# v2-scratch.net
KiCad netlist of a schematic drawn in EAGLE
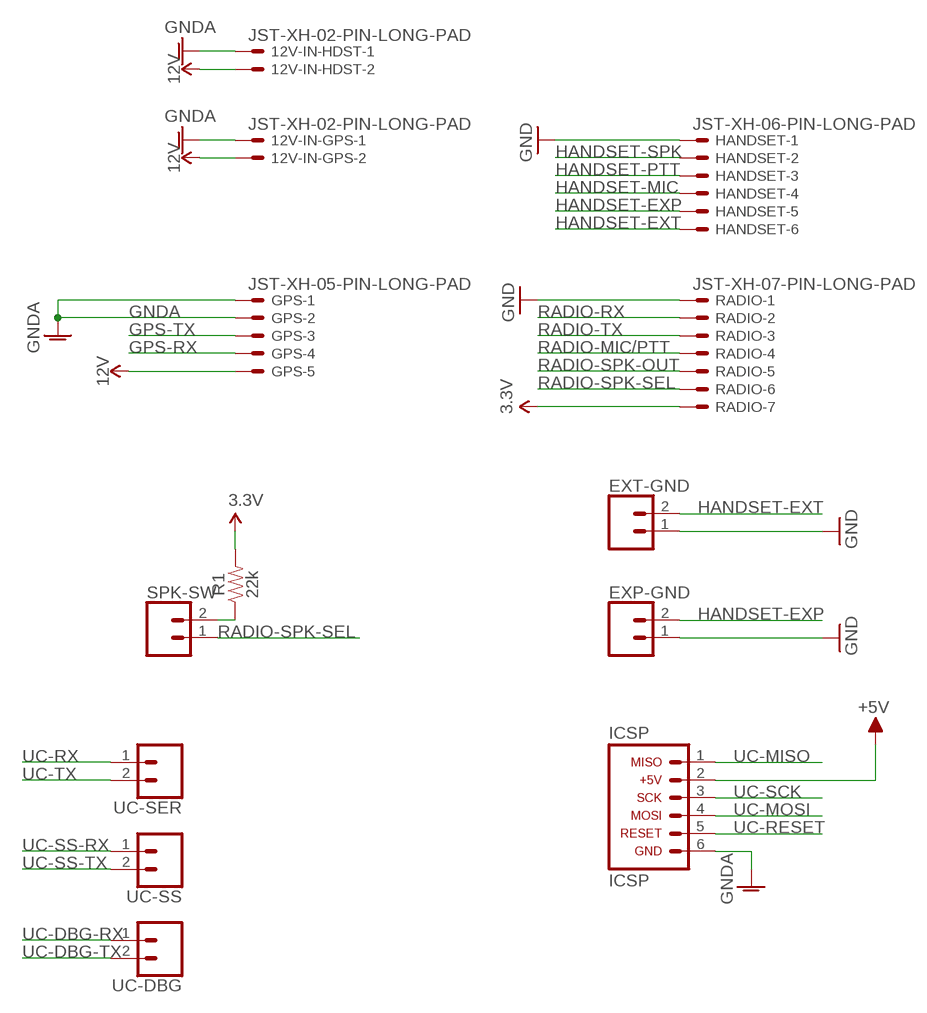
[diagram p0: schematic, sheet 1, part 1 of 2]
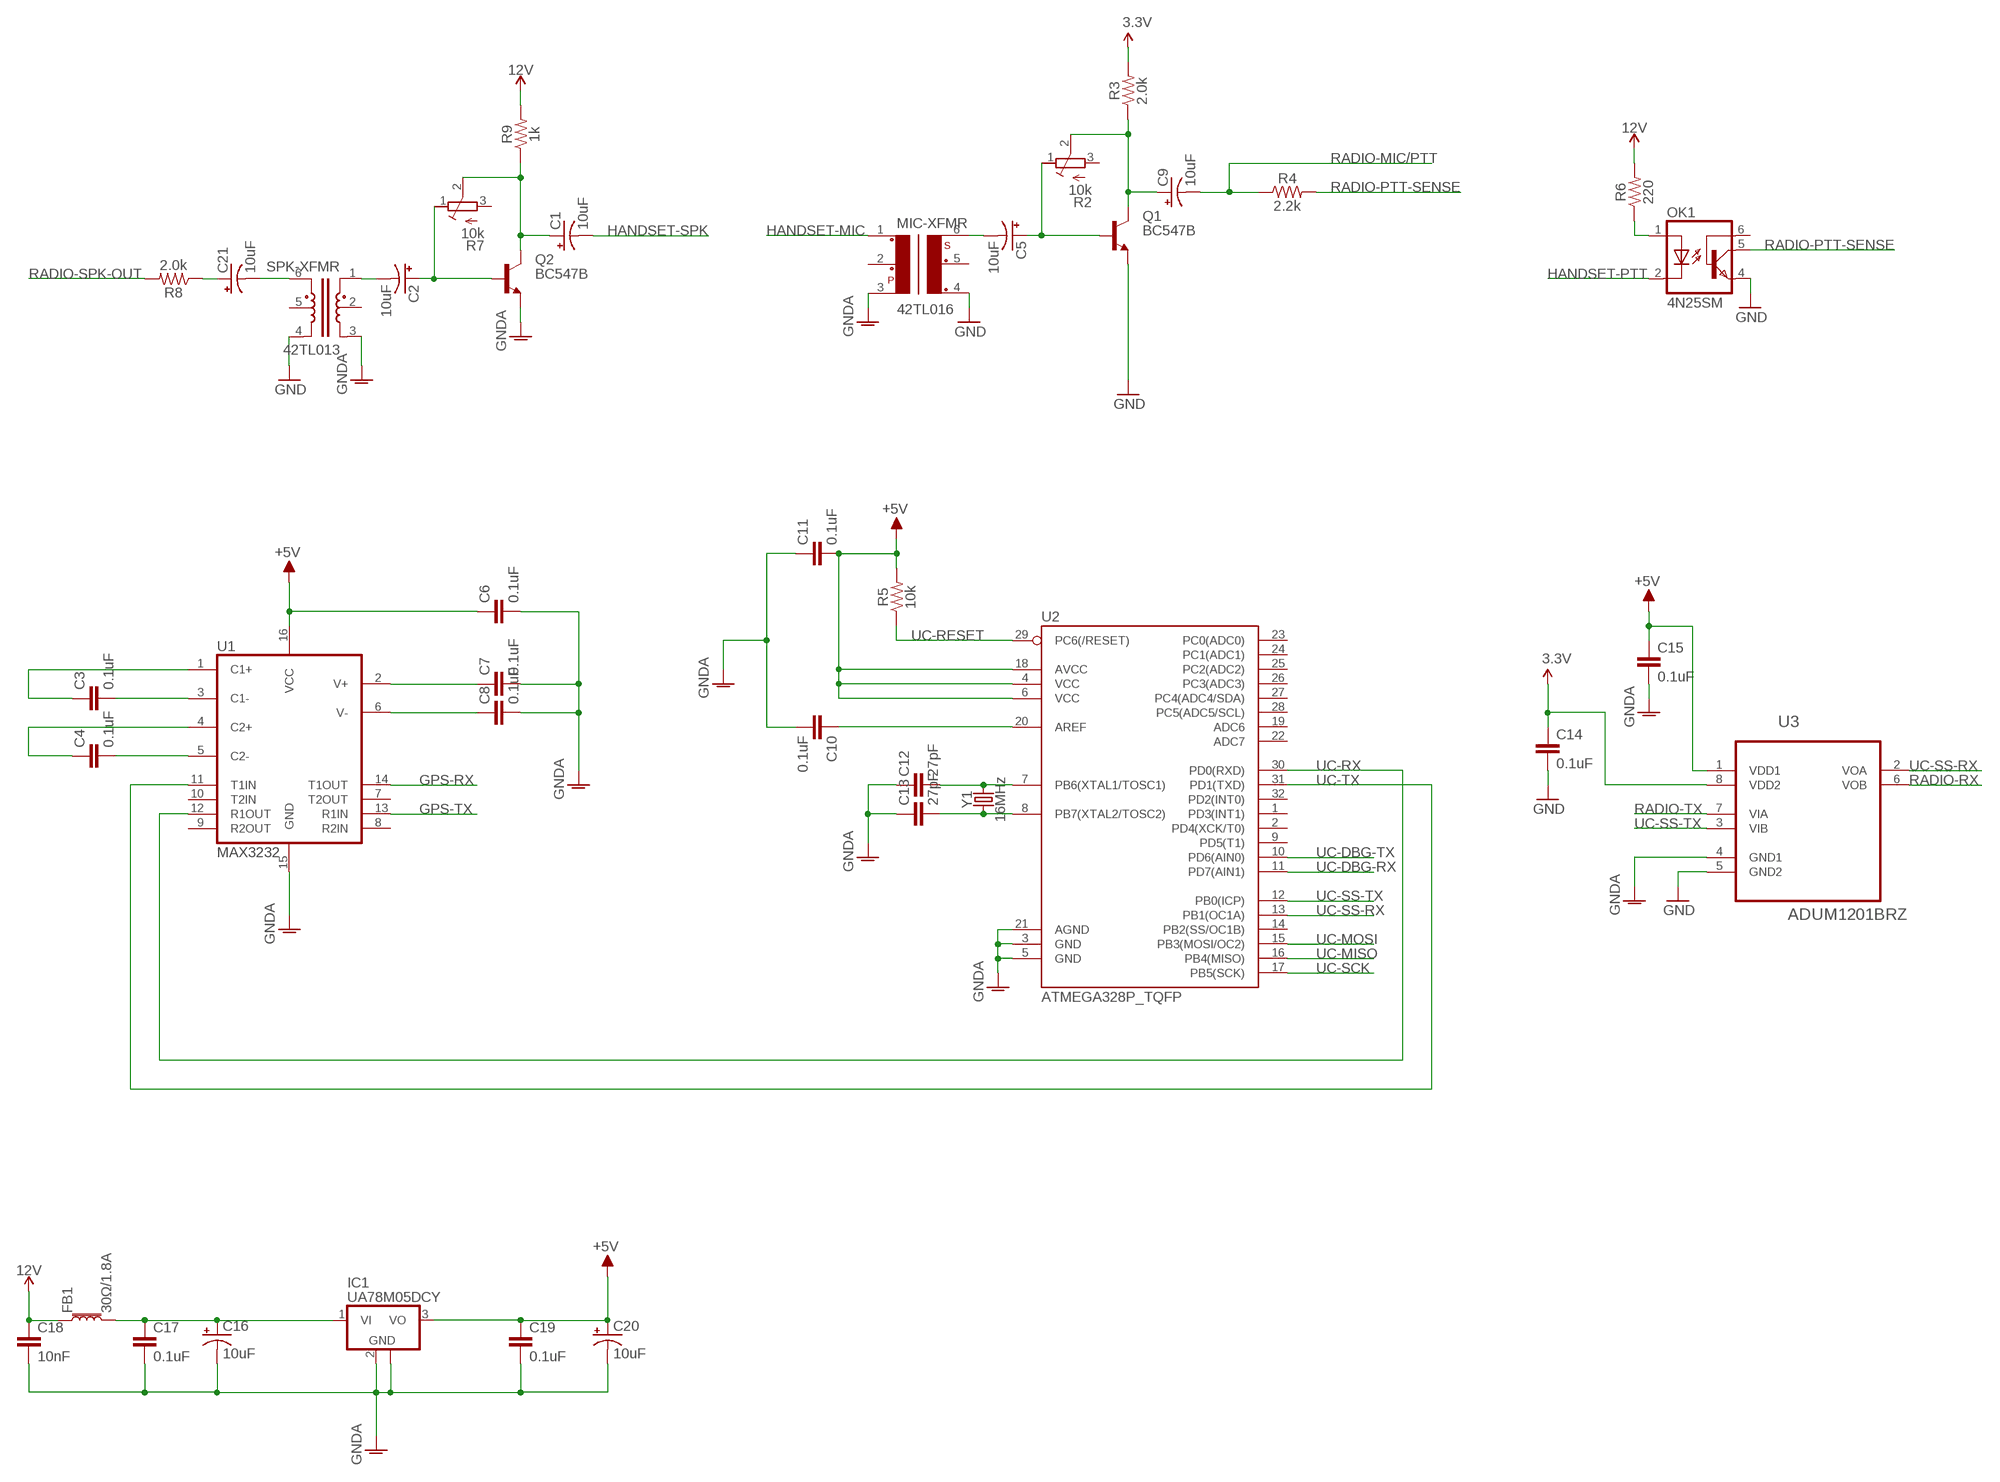
[diagram p1: schematic, sheet 1, part 2 of 2]

(export (version "E")
  (design (tool "Eeschema 10.0.6"))
  (components
    (comp (ref "12V-IN-GPS")
      (value "JST-XH-02-PIN-LONG-PAD")
      (footprint "eagle-import:JST-XH-02-PACKAGE-LONG-PAD")
      (libsource (lib "eagle-import") (part "JST-XH-02-PIN-LONG-PAD"))
    )
    (comp (ref "12V-IN-HDST")
      (value "JST-XH-02-PIN-LONG-PAD")
      (footprint "eagle-import:JST-XH-02-PACKAGE-LONG-PAD")
      (libsource (lib "eagle-import") (part "JST-XH-02-PIN-LONG-PAD"))
    )
    (comp (ref "C1")
      (value "10uF")
      (footprint "eagle-import:E2,5-5")
      (libsource (lib "eagle-import") (part "CPOL-USE2.5-5"))
    )
    (comp (ref "C2")
      (value "10uF")
      (footprint "eagle-import:E2,5-5")
      (libsource (lib "eagle-import") (part "CPOL-USE2.5-5"))
    )
    (comp (ref "C3")
      (value "0.1uF")
      (footprint "eagle-import:0603")
      (libsource (lib "eagle-import") (part "0.1UF-0603-25V-5%"))
    )
    (comp (ref "C4")
      (value "0.1uF")
      (footprint "eagle-import:0603")
      (libsource (lib "eagle-import") (part "0.1UF-0603-25V-5%"))
    )
    (comp (ref "C5")
      (value "10uF")
      (footprint "eagle-import:E2,5-5")
      (libsource (lib "eagle-import") (part "CPOL-USE2.5-5"))
    )
    (comp (ref "C6")
      (value "0.1uF")
      (footprint "eagle-import:0603")
      (libsource (lib "eagle-import") (part "0.1UF-0603-25V-5%"))
    )
    (comp (ref "C7")
      (value "0.1uF")
      (footprint "eagle-import:0603")
      (libsource (lib "eagle-import") (part "0.1UF-0603-25V-5%"))
    )
    (comp (ref "C8")
      (value "0.1uF")
      (footprint "eagle-import:0603")
      (libsource (lib "eagle-import") (part "0.1UF-0603-25V-5%"))
    )
    (comp (ref "C9")
      (value "10uF")
      (footprint "eagle-import:E2,5-5")
      (libsource (lib "eagle-import") (part "CPOL-USE2.5-5"))
    )
    (comp (ref "C10")
      (value "0.1uF")
      (footprint "eagle-import:0603")
      (libsource (lib "eagle-import") (part "0.1UF-0603-25V-5%"))
    )
    (comp (ref "C11")
      (value "0.1uF")
      (footprint "eagle-import:0603")
      (libsource (lib "eagle-import") (part "0.1UF-0603-25V-5%"))
    )
    (comp (ref "C12")
      (value "27pF")
      (footprint "eagle-import:0603")
      (libsource (lib "eagle-import") (part "27PF-0603-50V-5%"))
    )
    (comp (ref "C13")
      (value "27pF")
      (footprint "eagle-import:0603")
      (libsource (lib "eagle-import") (part "27PF-0603-50V-5%"))
    )
    (comp (ref "C14")
      (value "0.1uF")
      (footprint "eagle-import:0603")
      (libsource (lib "eagle-import") (part "0.1UF-0603-25V-5%"))
    )
    (comp (ref "C15")
      (value "0.1uF")
      (footprint "eagle-import:0603")
      (libsource (lib "eagle-import") (part "0.1UF-0603-25V-5%"))
    )
    (comp (ref "C16")
      (value "10uF")
      (footprint "eagle-import:E2,5-5")
      (libsource (lib "eagle-import") (part "CPOL-USE2.5-5"))
    )
    (comp (ref "C17")
      (value "0.1uF")
      (footprint "eagle-import:0603")
      (libsource (lib "eagle-import") (part "0.1UF-0603-25V-5%"))
    )
    (comp (ref "C18")
      (value "10nF")
      (footprint "eagle-import:0603")
      (libsource (lib "eagle-import") (part "10NF-0603-50V-10%"))
    )
    (comp (ref "C19")
      (value "0.1uF")
      (footprint "eagle-import:0603")
      (libsource (lib "eagle-import") (part "0.1UF-0603-25V-5%"))
    )
    (comp (ref "C20")
      (value "10uF")
      (footprint "eagle-import:E2,5-5")
      (libsource (lib "eagle-import") (part "CPOL-USE2.5-5"))
    )
    (comp (ref "C21")
      (value "10uF")
      (footprint "eagle-import:E2,5-5")
      (libsource (lib "eagle-import") (part "CPOL-USE2.5-5"))
    )
    (comp (ref "EXP-GND")
      (value "CONN_02")
      (footprint "eagle-import:1X02")
      (libsource (lib "eagle-import") (part "CONN_02"))
    )
    (comp (ref "EXT-GND")
      (value "CONN_02")
      (footprint "eagle-import:1X02")
      (libsource (lib "eagle-import") (part "CONN_02"))
    )
    (comp (ref "FB1")
      (value "30Ω/1.8A")
      (footprint "eagle-import:0603")
      (libsource (lib "eagle-import") (part "FERRITE_BEAD-0603"))
    )
    (comp (ref "GPS")
      (value "JST-XH-05-PIN-LONG-PAD")
      (footprint "eagle-import:JST-XH-05-PACKAGE-LONG-PAD")
      (libsource (lib "eagle-import") (part "JST-XH-05-PIN-LONG-PAD"))
    )
    (comp (ref "HANDSET")
      (value "JST-XH-06-PIN-LONG-PAD")
      (footprint "eagle-import:JST-XH-06-PACKAGE-LONG-PAD")
      (libsource (lib "eagle-import") (part "JST-XH-06-PIN-LONG-PAD"))
    )
    (comp (ref "IC1")
      (value "UA78M05DCY")
      (footprint "eagle-import:SOT223")
      (libsource (lib "eagle-import") (part "UA78MDCY05"))
    )
    (comp (ref "ICSP")
      (value "ARDUINO_CONN-ICSP")
      (footprint "eagle-import:CONN-2X03")
      (libsource (lib "eagle-import") (part "ARDUINO_CONN-ICSP"))
    )
    (comp (ref "MIC-XFMR")
      (value "42TL016")
      (footprint "eagle-import:42TL")
      (libsource (lib "eagle-import") (part "42T?L016"))
    )
    (comp (ref "OK1")
      (value "4N25SM")
      (footprint "eagle-import:DIL6-SMD")
      (fields (field (name "MF") "FAIRCHILD SEMICONDUCTOR"))
      (libsource (lib "eagle-import") (part "4N?MS25"))
    )
    (comp (ref "Q1")
      (value "BC547B")
      (footprint "eagle-import:TO92")
      (libsource (lib "eagle-import") (part "BC547B"))
    )
    (comp (ref "Q2")
      (value "BC547B")
      (footprint "eagle-import:TO92")
      (libsource (lib "eagle-import") (part "BC547B"))
    )
    (comp (ref "R1")
      (value "22k")
      (footprint "eagle-import:0603")
      (libsource (lib "eagle-import") (part "22KOHM-0603-1/10W-1%"))
    )
    (comp (ref "R2")
      (value "10k")
      (footprint "eagle-import:RTRIMT93YA")
      (libsource (lib "eagle-import") (part "R-TRIMMT93YA"))
    )
    (comp (ref "R3")
      (value "2.0k")
      (footprint "eagle-import:0603")
      (libsource (lib "eagle-import") (part "2.0KOHM-0603-1/10W-5%"))
    )
    (comp (ref "R4")
      (value "2.2k")
      (footprint "eagle-import:0603")
      (libsource (lib "eagle-import") (part "2.2KOHM-0603-1/10W-1%"))
    )
    (comp (ref "R5")
      (value "10k")
      (footprint "eagle-import:0603")
      (libsource (lib "eagle-import") (part "10KOHM-0603-1/10W-1%"))
    )
    (comp (ref "R6")
      (value "220")
      (footprint "eagle-import:0603")
      (libsource (lib "eagle-import") (part "220OHM-0603-1/10W-1%"))
    )
    (comp (ref "R7")
      (value "10k")
      (footprint "eagle-import:RTRIMT93YA")
      (libsource (lib "eagle-import") (part "R-TRIMMT93YA"))
    )
    (comp (ref "R8")
      (value "2.0k")
      (footprint "eagle-import:0603")
      (libsource (lib "eagle-import") (part "2.0KOHM-0603-1/10W-5%"))
    )
    (comp (ref "R9")
      (value "1k")
      (footprint "eagle-import:0603")
      (libsource (lib "eagle-import") (part "1KOHM-0603-1/10W-1%"))
    )
    (comp (ref "RADIO")
      (value "JST-XH-07-PIN-LONG-PAD")
      (footprint "eagle-import:JST-XH-07-PACKAGE-LONG-PAD")
      (libsource (lib "eagle-import") (part "JST-XH-07-PIN-LONG-PAD"))
    )
    (comp (ref "SPK-SW")
      (value "CONN_02")
      (footprint "eagle-import:1X02")
      (libsource (lib "eagle-import") (part "CONN_02"))
    )
    (comp (ref "SPK-XFMR")
      (value "42TL013")
      (footprint "eagle-import:TRANS_EI-14")
      (libsource (lib "eagle-import") (part "42TL013"))
    )
    (comp (ref "U1")
      (value "MAX3232")
      (footprint "eagle-import:SO16")
      (libsource (lib "eagle-import") (part "MAX2323SOIC16"))
    )
    (comp (ref "U2")
      (value "ATMEGA328P_TQFP")
      (footprint "eagle-import:TQFP32-08")
      (libsource (lib "eagle-import") (part "ATMEGA328P_TQFP"))
    )
    (comp (ref "U3")
      (value "ADUM1201BRZ")
      (footprint "eagle-import:SOIC127P600X175-8N")
      (libsource (lib "eagle-import") (part "ADUM1201BRZ"))
    )
    (comp (ref "UC-DBG")
      (value "CONN_02")
      (footprint "eagle-import:1X02")
      (libsource (lib "eagle-import") (part "CONN_02"))
    )
    (comp (ref "UC-SER")
      (value "CONN_02")
      (footprint "eagle-import:1X02")
      (libsource (lib "eagle-import") (part "CONN_02"))
    )
    (comp (ref "UC-SS")
      (value "CONN_02")
      (footprint "eagle-import:1X02")
      (libsource (lib "eagle-import") (part "CONN_02"))
    )
    (comp (ref "Y1")
      (value "16MHz")
      (footprint "eagle-import:HC49US")
      (libsource (lib "eagle-import") (part "CRYSTAL-16MHZPTH-HC49US"))
    )
  )
  (nets
    (net (code "1") (name "+5V") (class "Default")
      (node (ref "C11") (pin "2") (pinfunction "2_2") (pintype "passive"))
      (node (ref "C15") (pin "1") (pinfunction "1_1") (pintype "passive"))
      (node (ref "C19") (pin "1") (pinfunction "1_1") (pintype "passive"))
      (node (ref "C20") (pin "+") (pinfunction "+_+") (pintype "passive"))
      (node (ref "C6") (pin "1") (pinfunction "1_1") (pintype "passive"))
      (node (ref "IC1") (pin "3") (pinfunction "VO_3") (pintype "passive"))
      (node (ref "ICSP") (pin "2") (pinfunction "2_2") (pintype "passive"))
      (node (ref "R5") (pin "2") (pinfunction "2_2") (pintype "passive"))
      (node (ref "U1") (pin "16") (pinfunction "VCC_16") (pintype "bidirectional"))
      (node (ref "U2") (pin "18") (pinfunction "AVCC_18") (pintype "bidirectional"))
      (node (ref "U2") (pin "4") (pinfunction "VCC_4") (pintype "bidirectional"))
      (node (ref "U2") (pin "6") (pinfunction "VCC_6") (pintype "bidirectional"))
      (node (ref "U3") (pin "1") (pinfunction "VDD1_1") (pintype "power_in"))
    )
    (net (code "2") (name "/GPS-RX") (class "Default")
      (node (ref "GPS") (pin "4") (pinfunction "S_4") (pintype "passive"))
      (node (ref "U1") (pin "14") (pinfunction "T1OUT_14") (pintype "output"))
    )
    (net (code "3") (name "/GPS-TX") (class "Default")
      (node (ref "GPS") (pin "3") (pinfunction "S_3") (pintype "passive"))
      (node (ref "U1") (pin "13") (pinfunction "R1IN_13") (pintype "input"))
    )
    (net (code "4") (name "/HANDSET-EXP") (class "Default")
      (node (ref "EXP-GND") (pin "2") (pinfunction "2_2") (pintype "passive"))
      (node (ref "HANDSET") (pin "5") (pinfunction "S_5") (pintype "passive"))
    )
    (net (code "5") (name "/HANDSET-EXT") (class "Default")
      (node (ref "EXT-GND") (pin "2") (pinfunction "2_2") (pintype "passive"))
      (node (ref "HANDSET") (pin "6") (pinfunction "S_6") (pintype "passive"))
    )
    (net (code "6") (name "/HANDSET-MIC") (class "Default")
      (node (ref "HANDSET") (pin "4") (pinfunction "S_4") (pintype "passive"))
      (node (ref "MIC-XFMR") (pin "1") (pinfunction "1_1") (pintype "passive"))
    )
    (net (code "7") (name "/HANDSET-PTT") (class "Default")
      (node (ref "HANDSET") (pin "3") (pinfunction "S_3") (pintype "passive"))
      (node (ref "OK1") (pin "2") (pinfunction "C_2") (pintype "passive"))
    )
    (net (code "8") (name "/HANDSET-SPK") (class "Default")
      (node (ref "C1") (pin "-") (pinfunction "-_-") (pintype "passive"))
      (node (ref "HANDSET") (pin "2") (pinfunction "S_2") (pintype "passive"))
    )
    (net (code "9") (name "/RADIO-MIC{slash}PTT") (class "Default")
      (node (ref "C9") (pin "-") (pinfunction "-_-") (pintype "passive"))
      (node (ref "R4") (pin "1") (pinfunction "1_1") (pintype "passive"))
      (node (ref "RADIO") (pin "4") (pinfunction "S_4") (pintype "passive"))
    )
    (net (code "10") (name "/RADIO-PTT-SENSE") (class "Default")
      (node (ref "OK1") (pin "5") (pinfunction "COL_5") (pintype "passive"))
      (node (ref "R4") (pin "2") (pinfunction "2_2") (pintype "passive"))
    )
    (net (code "11") (name "/RADIO-RX") (class "Default")
      (node (ref "RADIO") (pin "2") (pinfunction "S_2") (pintype "passive"))
      (node (ref "U3") (pin "6") (pinfunction "VOB_6") (pintype "output"))
    )
    (net (code "12") (name "/RADIO-SPK-OUT") (class "Default")
      (node (ref "R8") (pin "2") (pinfunction "2_2") (pintype "passive"))
      (node (ref "RADIO") (pin "5") (pinfunction "S_5") (pintype "passive"))
    )
    (net (code "13") (name "/RADIO-SPK-SEL") (class "Default")
      (node (ref "RADIO") (pin "6") (pinfunction "S_6") (pintype "passive"))
      (node (ref "SPK-SW") (pin "1") (pinfunction "1_1") (pintype "passive"))
    )
    (net (code "14") (name "/RADIO-TX") (class "Default")
      (node (ref "RADIO") (pin "3") (pinfunction "S_3") (pintype "passive"))
      (node (ref "U3") (pin "7") (pinfunction "VIA_7") (pintype "input"))
    )
    (net (code "15") (name "/UC-DBG-RX") (class "Default")
      (node (ref "U2") (pin "11") (pinfunction "PD7(AIN1)_11") (pintype "bidirectional"))
      (node (ref "UC-DBG") (pin "1") (pinfunction "1_1") (pintype "passive"))
    )
    (net (code "16") (name "/UC-DBG-TX") (class "Default")
      (node (ref "U2") (pin "10") (pinfunction "PD6(AIN0)_10") (pintype "bidirectional"))
      (node (ref "UC-DBG") (pin "2") (pinfunction "2_2") (pintype "passive"))
    )
    (net (code "17") (name "/UC-MISO") (class "Default")
      (node (ref "ICSP") (pin "1") (pinfunction "1_1") (pintype "passive"))
      (node (ref "U2") (pin "16") (pinfunction "PB4(MISO)_16") (pintype "bidirectional"))
    )
    (net (code "18") (name "/UC-MOSI") (class "Default")
      (node (ref "ICSP") (pin "4") (pinfunction "4_4") (pintype "passive"))
      (node (ref "U2") (pin "15") (pinfunction "PB3(MOSI/OC2)_15") (pintype "bidirectional"))
    )
    (net (code "19") (name "/UC-RESET") (class "Default")
      (node (ref "ICSP") (pin "5") (pinfunction "5_5") (pintype "passive"))
      (node (ref "R5") (pin "1") (pinfunction "1_1") (pintype "passive"))
      (node (ref "U2") (pin "29") (pinfunction "PC6(/RESET)_29") (pintype "bidirectional"))
    )
    (net (code "20") (name "/UC-RX") (class "Default")
      (node (ref "U1") (pin "12") (pinfunction "R1OUT_12") (pintype "output"))
      (node (ref "U2") (pin "30") (pinfunction "PD0(RXD)_30") (pintype "bidirectional"))
      (node (ref "UC-SER") (pin "1") (pinfunction "1_1") (pintype "passive"))
    )
    (net (code "21") (name "/UC-SCK") (class "Default")
      (node (ref "ICSP") (pin "3") (pinfunction "3_3") (pintype "passive"))
      (node (ref "U2") (pin "17") (pinfunction "PB5(SCK)_17") (pintype "bidirectional"))
    )
    (net (code "22") (name "/UC-SS-RX") (class "Default")
      (node (ref "U2") (pin "13") (pinfunction "PB1(OC1A)_13") (pintype "bidirectional"))
      (node (ref "U3") (pin "2") (pinfunction "VOA_2") (pintype "output"))
      (node (ref "UC-SS") (pin "1") (pinfunction "1_1") (pintype "passive"))
    )
    (net (code "23") (name "/UC-SS-TX") (class "Default")
      (node (ref "U2") (pin "12") (pinfunction "PB0(ICP)_12") (pintype "bidirectional"))
      (node (ref "U3") (pin "3") (pinfunction "VIB_3") (pintype "input"))
      (node (ref "UC-SS") (pin "2") (pinfunction "2_2") (pintype "passive"))
    )
    (net (code "24") (name "/UC-TX") (class "Default")
      (node (ref "U1") (pin "11") (pinfunction "T1IN_11") (pintype "input"))
      (node (ref "U2") (pin "31") (pinfunction "PD1(TXD)_31") (pintype "bidirectional"))
      (node (ref "UC-SER") (pin "2") (pinfunction "2_2") (pintype "passive"))
    )
    (net (code "25") (name "3.3V") (class "Default")
      (node (ref "C14") (pin "1") (pinfunction "1_1") (pintype "passive"))
      (node (ref "R1") (pin "2") (pinfunction "2_2") (pintype "passive"))
      (node (ref "R3") (pin "2") (pinfunction "2_2") (pintype "passive"))
      (node (ref "RADIO") (pin "7") (pinfunction "S_7") (pintype "passive"))
      (node (ref "U3") (pin "8") (pinfunction "VDD2_8") (pintype "power_in"))
    )
    (net (code "26") (name "12V") (class "Default")
      (node (ref "12V-IN-GPS") (pin "2") (pinfunction "S_2") (pintype "passive"))
      (node (ref "12V-IN-HDST") (pin "2") (pinfunction "S_2") (pintype "passive"))
      (node (ref "C18") (pin "1") (pinfunction "1_1") (pintype "passive"))
      (node (ref "FB1") (pin "1") (pinfunction "1_1") (pintype "passive"))
      (node (ref "GPS") (pin "5") (pinfunction "S_5") (pintype "passive"))
      (node (ref "R6") (pin "2") (pinfunction "2_2") (pintype "passive"))
      (node (ref "R9") (pin "2") (pinfunction "2_2") (pintype "passive"))
    )
    (net (code "27") (name "GND") (class "Default")
      (node (ref "C14") (pin "2") (pinfunction "2_2") (pintype "passive"))
      (node (ref "EXP-GND") (pin "1") (pinfunction "1_1") (pintype "passive"))
      (node (ref "EXT-GND") (pin "1") (pinfunction "1_1") (pintype "passive"))
      (node (ref "HANDSET") (pin "1") (pinfunction "S_1") (pintype "passive"))
      (node (ref "MIC-XFMR") (pin "4") (pinfunction "4_4") (pintype "passive"))
      (node (ref "OK1") (pin "4") (pinfunction "EMI_4") (pintype "passive"))
      (node (ref "Q1") (pin "1") (pinfunction "E_1") (pintype "passive"))
      (node (ref "RADIO") (pin "1") (pinfunction "S_1") (pintype "passive"))
      (node (ref "SPK-XFMR") (pin "4") (pinfunction "4_4") (pintype "passive"))
      (node (ref "U3") (pin "5") (pinfunction "GND2_5") (pintype "passive"))
    )
    (net (code "28") (name "GNDA") (class "Default")
      (node (ref "12V-IN-GPS") (pin "1") (pinfunction "S_1") (pintype "passive"))
      (node (ref "12V-IN-HDST") (pin "1") (pinfunction "S_1") (pintype "passive"))
      (node (ref "C10") (pin "2") (pinfunction "2_2") (pintype "passive"))
      (node (ref "C11") (pin "1") (pinfunction "1_1") (pintype "passive"))
      (node (ref "C12") (pin "1") (pinfunction "1_1") (pintype "passive"))
      (node (ref "C13") (pin "1") (pinfunction "1_1") (pintype "passive"))
      (node (ref "C15") (pin "2") (pinfunction "2_2") (pintype "passive"))
      (node (ref "C16") (pin "-") (pinfunction "-_-") (pintype "passive"))
      (node (ref "C17") (pin "2") (pinfunction "2_2") (pintype "passive"))
      (node (ref "C18") (pin "2") (pinfunction "2_2") (pintype "passive"))
      (node (ref "C19") (pin "2") (pinfunction "2_2") (pintype "passive"))
      (node (ref "C20") (pin "-") (pinfunction "-_-") (pintype "passive"))
      (node (ref "C6") (pin "2") (pinfunction "2_2") (pintype "passive"))
      (node (ref "C7") (pin "2") (pinfunction "2_2") (pintype "passive"))
      (node (ref "C8") (pin "2") (pinfunction "2_2") (pintype "passive"))
      (node (ref "GPS") (pin "1") (pinfunction "S_1") (pintype "passive"))
      (node (ref "GPS") (pin "2") (pinfunction "S_2") (pintype "passive"))
      (node (ref "IC1") (pin "2") (pinfunction "GND_2") (pintype "passive"))
      (node (ref "IC1") (pin "4") (pinfunction "GND_4") (pintype "passive"))
      (node (ref "ICSP") (pin "6") (pinfunction "6_6") (pintype "passive"))
      (node (ref "MIC-XFMR") (pin "3") (pinfunction "3_3") (pintype "passive"))
      (node (ref "Q2") (pin "1") (pinfunction "E_1") (pintype "passive"))
      (node (ref "SPK-XFMR") (pin "3") (pinfunction "3_3") (pintype "passive"))
      (node (ref "U1") (pin "15") (pinfunction "GND_15") (pintype "bidirectional"))
      (node (ref "U2") (pin "21") (pinfunction "AGND_21") (pintype "bidirectional"))
      (node (ref "U2") (pin "3") (pinfunction "GND_3") (pintype "bidirectional"))
      (node (ref "U2") (pin "5") (pinfunction "GND_5") (pintype "bidirectional"))
      (node (ref "U3") (pin "4") (pinfunction "GND1_4") (pintype "passive"))
    )
    (net (code "29") (name "Net-(C2-Pad-)") (class "Default")
      (node (ref "C2") (pin "-") (pinfunction "-_-") (pintype "passive"))
      (node (ref "SPK-XFMR") (pin "1") (pinfunction "1_1") (pintype "passive"))
    )
    (net (code "30") (name "Net-(C5-Pad-)") (class "Default")
      (node (ref "C5") (pin "-") (pinfunction "-_-") (pintype "passive"))
      (node (ref "MIC-XFMR") (pin "6") (pinfunction "6_6") (pintype "passive"))
    )
    (net (code "31") (name "Net-(C21-Pad+)") (class "Default")
      (node (ref "C21") (pin "+") (pinfunction "+_+") (pintype "passive"))
      (node (ref "R8") (pin "1") (pinfunction "1_1") (pintype "passive"))
    )
    (net (code "32") (name "Net-(C21-Pad-)") (class "Default")
      (node (ref "C21") (pin "-") (pinfunction "-_-") (pintype "passive"))
      (node (ref "SPK-XFMR") (pin "6") (pinfunction "6_6") (pintype "passive"))
    )
    (net (code "33") (name "Net-(IC1-VI)") (class "Default")
      (node (ref "C16") (pin "+") (pinfunction "+_+") (pintype "passive"))
      (node (ref "C17") (pin "1") (pinfunction "1_1") (pintype "passive"))
      (node (ref "FB1") (pin "2") (pinfunction "2_2") (pintype "passive"))
      (node (ref "IC1") (pin "1") (pinfunction "VI_1") (pintype "input"))
    )
    (net (code "34") (name "Net-(OK1-A)") (class "Default")
      (node (ref "OK1") (pin "1") (pinfunction "A_1") (pintype "passive"))
      (node (ref "R6") (pin "1") (pinfunction "1_1") (pintype "passive"))
    )
    (net (code "35") (name "Net-(Q1-B)") (class "Default")
      (node (ref "C5") (pin "+") (pinfunction "+_+") (pintype "passive"))
      (node (ref "Q1") (pin "2") (pinfunction "B_2") (pintype "passive"))
      (node (ref "R2") (pin "1") (pinfunction "E_1") (pintype "passive"))
    )
    (net (code "36") (name "Net-(Q1-C)") (class "Default")
      (node (ref "C9") (pin "+") (pinfunction "+_+") (pintype "passive"))
      (node (ref "Q1") (pin "3") (pinfunction "C_3") (pintype "passive"))
      (node (ref "R2") (pin "2") (pinfunction "S_2") (pintype "passive"))
      (node (ref "R3") (pin "1") (pinfunction "1_1") (pintype "passive"))
    )
    (net (code "37") (name "Net-(Q2-B)") (class "Default")
      (node (ref "C2") (pin "+") (pinfunction "+_+") (pintype "passive"))
      (node (ref "Q2") (pin "2") (pinfunction "B_2") (pintype "passive"))
      (node (ref "R7") (pin "1") (pinfunction "E_1") (pintype "passive"))
    )
    (net (code "38") (name "Net-(Q2-C)") (class "Default")
      (node (ref "C1") (pin "+") (pinfunction "+_+") (pintype "passive"))
      (node (ref "Q2") (pin "3") (pinfunction "C_3") (pintype "passive"))
      (node (ref "R7") (pin "2") (pinfunction "S_2") (pintype "passive"))
      (node (ref "R9") (pin "1") (pinfunction "1_1") (pintype "passive"))
    )
    (net (code "39") (name "Net-(R1-Pad1)") (class "Default")
      (node (ref "R1") (pin "1") (pinfunction "1_1") (pintype "passive"))
      (node (ref "SPK-SW") (pin "2") (pinfunction "2_2") (pintype "passive"))
    )
    (net (code "40") (name "Net-(U1-C1+)") (class "Default")
      (node (ref "C3") (pin "1") (pinfunction "1_1") (pintype "passive"))
      (node (ref "U1") (pin "1") (pinfunction "C1+_1") (pintype "bidirectional"))
    )
    (net (code "41") (name "Net-(U1-C1-)") (class "Default")
      (node (ref "C3") (pin "2") (pinfunction "2_2") (pintype "passive"))
      (node (ref "U1") (pin "3") (pinfunction "C1-_3") (pintype "bidirectional"))
    )
    (net (code "42") (name "Net-(U1-C2+)") (class "Default")
      (node (ref "C4") (pin "1") (pinfunction "1_1") (pintype "passive"))
      (node (ref "U1") (pin "4") (pinfunction "C2+_4") (pintype "bidirectional"))
    )
    (net (code "43") (name "Net-(U1-C2-)") (class "Default")
      (node (ref "C4") (pin "2") (pinfunction "2_2") (pintype "passive"))
      (node (ref "U1") (pin "5") (pinfunction "C2-_5") (pintype "bidirectional"))
    )
    (net (code "44") (name "Net-(U1-V+)") (class "Default")
      (node (ref "C7") (pin "1") (pinfunction "1_1") (pintype "passive"))
      (node (ref "U1") (pin "2") (pinfunction "V+_2") (pintype "bidirectional"))
    )
    (net (code "45") (name "Net-(U1-V-)") (class "Default")
      (node (ref "C8") (pin "1") (pinfunction "1_1") (pintype "passive"))
      (node (ref "U1") (pin "6") (pinfunction "V-_6") (pintype "bidirectional"))
    )
    (net (code "46") (name "Net-(U2-AREF)") (class "Default")
      (node (ref "C10") (pin "1") (pinfunction "1_1") (pintype "passive"))
      (node (ref "U2") (pin "20") (pinfunction "AREF_20") (pintype "bidirectional"))
    )
    (net (code "47") (name "Net-(U2-PB6(XTAL1{slash}TOSC1))") (class "Default")
      (node (ref "C12") (pin "2") (pinfunction "2_2") (pintype "passive"))
      (node (ref "U2") (pin "7") (pinfunction "PB6(XTAL1/TOSC1)_7") (pintype "bidirectional"))
      (node (ref "Y1") (pin "2") (pinfunction "2_2") (pintype "passive"))
    )
    (net (code "48") (name "Net-(U2-PB7(XTAL2{slash}TOSC2))") (class "Default")
      (node (ref "C13") (pin "2") (pinfunction "2_2") (pintype "passive"))
      (node (ref "U2") (pin "8") (pinfunction "PB7(XTAL2/TOSC2)_8") (pintype "bidirectional"))
      (node (ref "Y1") (pin "1") (pinfunction "1_1") (pintype "passive"))
    )
    (net (code "49") (name "unconnected-(MIC-XFMR-Pad2)") (class "Default")
      (node (ref "MIC-XFMR") (pin "2") (pinfunction "2_2") (pintype "passive"))
    )
    (net (code "50") (name "unconnected-(MIC-XFMR-Pad5)") (class "Default")
      (node (ref "MIC-XFMR") (pin "5") (pinfunction "5_5") (pintype "passive"))
    )
    (net (code "51") (name "unconnected-(OK1-BAS-Pad6)") (class "Default")
      (node (ref "OK1") (pin "6") (pinfunction "BAS_6") (pintype "passive"))
    )
    (net (code "52") (name "unconnected-(R2-A-Pad3)") (class "Default")
      (node (ref "R2") (pin "3") (pinfunction "A_3") (pintype "passive"))
    )
    (net (code "53") (name "unconnected-(R7-A-Pad3)") (class "Default")
      (node (ref "R7") (pin "3") (pinfunction "A_3") (pintype "passive"))
    )
    (net (code "54") (name "unconnected-(SPK-XFMR-Pad2)") (class "Default")
      (node (ref "SPK-XFMR") (pin "2") (pinfunction "2_2") (pintype "passive"))
    )
    (net (code "55") (name "unconnected-(SPK-XFMR-Pad5)") (class "Default")
      (node (ref "SPK-XFMR") (pin "5") (pinfunction "5_5") (pintype "passive"))
    )
    (net (code "56") (name "unconnected-(U1-R2IN-Pad8)") (class "Default")
      (node (ref "U1") (pin "8") (pinfunction "R2IN_8") (pintype "input"))
    )
    (net (code "57") (name "unconnected-(U1-R2OUT-Pad9)") (class "Default")
      (node (ref "U1") (pin "9") (pinfunction "R2OUT_9") (pintype "output"))
    )
    (net (code "58") (name "unconnected-(U1-T2IN-Pad10)") (class "Default")
      (node (ref "U1") (pin "10") (pinfunction "T2IN_10") (pintype "input"))
    )
    (net (code "59") (name "unconnected-(U1-T2OUT-Pad7)") (class "Default")
      (node (ref "U1") (pin "7") (pinfunction "T2OUT_7") (pintype "output"))
    )
    (net (code "60") (name "unconnected-(U2-ADC6-Pad19)") (class "Default")
      (node (ref "U2") (pin "19") (pinfunction "ADC6_19") (pintype "bidirectional"))
    )
    (net (code "61") (name "unconnected-(U2-ADC7-Pad22)") (class "Default")
      (node (ref "U2") (pin "22") (pinfunction "ADC7_22") (pintype "bidirectional"))
    )
    (net (code "62") (name "unconnected-(U2-PB2(SS{slash}OC1B)-Pad14)") (class "Default")
      (node (ref "U2") (pin "14") (pinfunction "PB2(SS/OC1B)_14") (pintype "bidirectional"))
    )
    (net (code "63") (name "unconnected-(U2-PC0(ADC0)-Pad23)") (class "Default")
      (node (ref "U2") (pin "23") (pinfunction "PC0(ADC0)_23") (pintype "bidirectional"))
    )
    (net (code "64") (name "unconnected-(U2-PC1(ADC1)-Pad24)") (class "Default")
      (node (ref "U2") (pin "24") (pinfunction "PC1(ADC1)_24") (pintype "bidirectional"))
    )
    (net (code "65") (name "unconnected-(U2-PC2(ADC2)-Pad25)") (class "Default")
      (node (ref "U2") (pin "25") (pinfunction "PC2(ADC2)_25") (pintype "bidirectional"))
    )
    (net (code "66") (name "unconnected-(U2-PC3(ADC3)-Pad26)") (class "Default")
      (node (ref "U2") (pin "26") (pinfunction "PC3(ADC3)_26") (pintype "bidirectional"))
    )
    (net (code "67") (name "unconnected-(U2-PC4(ADC4{slash}SDA)-Pad27)") (class "Default")
      (node (ref "U2") (pin "27") (pinfunction "PC4(ADC4/SDA)_27") (pintype "bidirectional"))
    )
    (net (code "68") (name "unconnected-(U2-PC5(ADC5{slash}SCL)-Pad28)") (class "Default")
      (node (ref "U2") (pin "28") (pinfunction "PC5(ADC5/SCL)_28") (pintype "bidirectional"))
    )
    (net (code "69") (name "unconnected-(U2-PD2(INT0)-Pad32)") (class "Default")
      (node (ref "U2") (pin "32") (pinfunction "PD2(INT0)_32") (pintype "bidirectional"))
    )
    (net (code "70") (name "unconnected-(U2-PD3(INT1)-Pad1)") (class "Default")
      (node (ref "U2") (pin "1") (pinfunction "PD3(INT1)_1") (pintype "bidirectional"))
    )
    (net (code "71") (name "unconnected-(U2-PD4(XCK{slash}T0)-Pad2)") (class "Default")
      (node (ref "U2") (pin "2") (pinfunction "PD4(XCK/T0)_2") (pintype "bidirectional"))
    )
    (net (code "72") (name "unconnected-(U2-PD5(T1)-Pad9)") (class "Default")
      (node (ref "U2") (pin "9") (pinfunction "PD5(T1)_9") (pintype "bidirectional"))
    )
  )
)
